# Regulators.net
KiCad netlist of a schematic drawn in Altium Designer
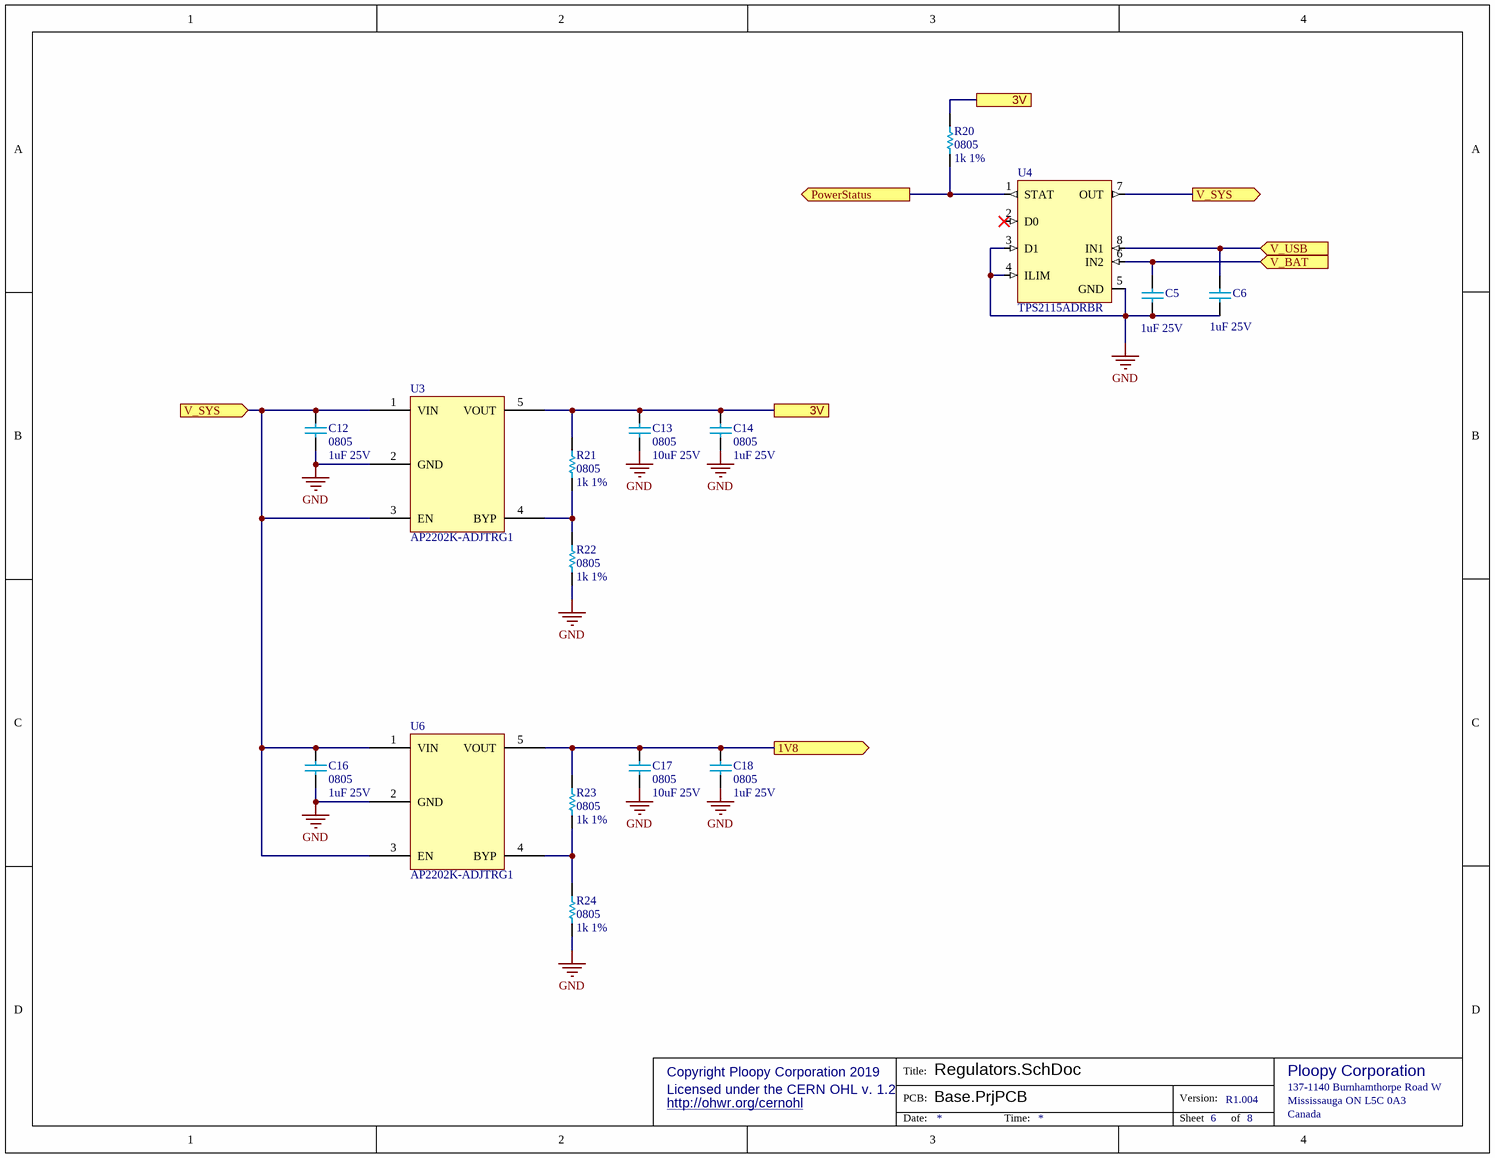
[diagram p0: Regulators.SchDoc]

(export (version "E")
  (design (tool "Eeschema 10.0.6"))
  (components
    (comp (ref "C5")
      (value "1uF 25V")
      (footprint "C0603")
      (description "0805, X5R or better")
      (fields (field (name "Comment") "0805"))
      (libsource (lib "Chip_Passives") (part "Cap 1uF 25V"))
    )
    (comp (ref "C6")
      (value "1uF 25V")
      (footprint "C0603")
      (description "0805, X5R or better")
      (fields (field (name "Comment") "0805"))
      (libsource (lib "Chip_Passives") (part "Cap 1uF 25V"))
    )
    (comp (ref "C12")
      (value "0805")
      (footprint "C0603")
      (description "0805, X5R or better")
      (fields (field (name "ALTIUM_VALUE") "1uF 25V"))
      (libsource (lib "Chip_Passives") (part "Cap 1uF 25V"))
    )
    (comp (ref "C13")
      (value "0805")
      (footprint "C0603")
      (description "0805, X5R or better")
      (fields (field (name "ALTIUM_VALUE") "10uF 25V"))
      (libsource (lib "Chip_Passives") (part "Cap 10uF 25V"))
    )
    (comp (ref "C14")
      (value "0805")
      (footprint "C0603")
      (description "0805, X5R or better")
      (fields (field (name "ALTIUM_VALUE") "1uF 25V"))
      (libsource (lib "Chip_Passives") (part "Cap 1uF 25V"))
    )
    (comp (ref "C16")
      (value "0805")
      (footprint "C0603")
      (description "0805, X5R or better")
      (fields (field (name "ALTIUM_VALUE") "1uF 25V"))
      (libsource (lib "Chip_Passives") (part "Cap 1uF 25V"))
    )
    (comp (ref "C17")
      (value "0805")
      (footprint "C0603")
      (description "0805, X5R or better")
      (fields (field (name "ALTIUM_VALUE") "10uF 25V"))
      (libsource (lib "Chip_Passives") (part "Cap 10uF 25V"))
    )
    (comp (ref "C18")
      (value "0805")
      (footprint "C0603")
      (description "0805, X5R or better")
      (fields (field (name "ALTIUM_VALUE") "1uF 25V"))
      (libsource (lib "Chip_Passives") (part "Cap 1uF 25V"))
    )
    (comp (ref "R20")
      (value "0805")
      (footprint "0603")
      (description "Chip resistor, 1/8W 100PPM")
      (fields (field (name "ALTIUM_VALUE") "1k 1%"))
      (libsource (lib "Chip_Passives") (part "Res 1k 1% 0805"))
    )
    (comp (ref "R21")
      (value "0805")
      (footprint "0603")
      (description "Chip resistor, 1/8W 100PPM")
      (fields (field (name "ALTIUM_VALUE") "1k 1%"))
      (libsource (lib "Chip_Passives") (part "Res 1k 1% 0805"))
    )
    (comp (ref "R22")
      (value "0805")
      (footprint "0603")
      (description "Chip resistor, 1/8W 100PPM")
      (fields (field (name "ALTIUM_VALUE") "1k 1%"))
      (libsource (lib "Chip_Passives") (part "Res 1k 1% 0805"))
    )
    (comp (ref "R23")
      (value "0805")
      (footprint "0603")
      (description "Chip resistor, 1/8W 100PPM")
      (fields (field (name "ALTIUM_VALUE") "1k 1%"))
      (libsource (lib "Chip_Passives") (part "Res 1k 1% 0805"))
    )
    (comp (ref "R24")
      (value "0805")
      (footprint "0603")
      (description "Chip resistor, 1/8W 100PPM")
      (fields (field (name "ALTIUM_VALUE") "1k 1%"))
      (libsource (lib "Chip_Passives") (part "Res 1k 1% 0805"))
    )
    (comp (ref "U3")
      (value "AP2202K-ADJTRG1")
      (footprint "AP2202 - SOT95P270X145-5N")
      (description "3.3V 150mA LDO regulator")
      (libsource (lib "PowerSupply") (part "AP2202K-3.3"))
    )
    (comp (ref "U4")
      (value "TPS2115ADRBR")
      (footprint "TSSOP-8")
      (libsource (lib "Schlib1") (part "TPS2115ADRBR"))
    )
    (comp (ref "U6")
      (value "AP2202K-ADJTRG1")
      (footprint "AP2202 - SOT95P270X145-5N")
      (description "3.3V 150mA LDO regulator")
      (libsource (lib "PowerSupply") (part "AP2202K-3.3"))
    )
  )
  (nets
    (net (code "1") (name "/1V8") (class "Default")
      (node (ref "C17") (pin "2") (pinfunction "2_2") (pintype "passive"))
      (node (ref "C18") (pin "2") (pinfunction "2_2") (pintype "passive"))
      (node (ref "R23") (pin "2") (pinfunction "2_2") (pintype "passive"))
      (node (ref "U6") (pin "5") (pinfunction "VOUT_5") (pintype "passive"))
    )
    (net (code "2") (name "/3V") (class "Default")
      (node (ref "C13") (pin "2") (pinfunction "2_2") (pintype "passive"))
      (node (ref "C14") (pin "2") (pinfunction "2_2") (pintype "passive"))
      (node (ref "R20") (pin "2") (pinfunction "2_2") (pintype "passive"))
      (node (ref "R21") (pin "2") (pinfunction "2_2") (pintype "passive"))
      (node (ref "U3") (pin "5") (pinfunction "VOUT_5") (pintype "passive"))
    )
    (net (code "3") (name "/PowerStatus") (class "Default")
      (node (ref "R20") (pin "1") (pinfunction "1_1") (pintype "passive"))
      (node (ref "U4") (pin "1") (pinfunction "STAT_1") (pintype "output"))
    )
    (net (code "4") (name "/V_BAT") (class "Default")
      (node (ref "C5") (pin "2") (pinfunction "2_2") (pintype "passive"))
      (node (ref "U4") (pin "6") (pinfunction "IN2_6") (pintype "input"))
    )
    (net (code "5") (name "/V_SYS") (class "Default")
      (node (ref "C12") (pin "2") (pinfunction "2_2") (pintype "passive"))
      (node (ref "C16") (pin "2") (pinfunction "2_2") (pintype "passive"))
      (node (ref "U3") (pin "1") (pinfunction "VIN_1") (pintype "passive"))
      (node (ref "U3") (pin "3") (pinfunction "EN_3") (pintype "passive"))
      (node (ref "U4") (pin "7") (pinfunction "OUT_7") (pintype "output"))
      (node (ref "U6") (pin "1") (pinfunction "VIN_1") (pintype "passive"))
      (node (ref "U6") (pin "3") (pinfunction "EN_3") (pintype "passive"))
    )
    (net (code "6") (name "/V_USB") (class "Default")
      (node (ref "C6") (pin "2") (pinfunction "2_2") (pintype "passive"))
      (node (ref "U4") (pin "8") (pinfunction "IN1_8") (pintype "input"))
    )
    (net (code "7") (name "GND") (class "Default")
      (node (ref "C12") (pin "1") (pinfunction "1_1") (pintype "passive"))
      (node (ref "C13") (pin "1") (pinfunction "1_1") (pintype "passive"))
      (node (ref "C14") (pin "1") (pinfunction "1_1") (pintype "passive"))
      (node (ref "C16") (pin "1") (pinfunction "1_1") (pintype "passive"))
      (node (ref "C17") (pin "1") (pinfunction "1_1") (pintype "passive"))
      (node (ref "C18") (pin "1") (pinfunction "1_1") (pintype "passive"))
      (node (ref "C5") (pin "1") (pinfunction "1_1") (pintype "passive"))
      (node (ref "C6") (pin "1") (pinfunction "1_1") (pintype "passive"))
      (node (ref "R22") (pin "1") (pinfunction "1_1") (pintype "passive"))
      (node (ref "R24") (pin "1") (pinfunction "1_1") (pintype "passive"))
      (node (ref "U3") (pin "2") (pinfunction "GND_2") (pintype "passive"))
      (node (ref "U4") (pin "3") (pinfunction "D1_3") (pintype "input"))
      (node (ref "U4") (pin "4") (pinfunction "ILIM_4") (pintype "input"))
      (node (ref "U4") (pin "5") (pinfunction "GND_5") (pintype "power_in"))
      (node (ref "U6") (pin "2") (pinfunction "GND_2") (pintype "passive"))
    )
    (net (code "8") (name "Net-(U3-BYP)") (class "Default")
      (node (ref "R21") (pin "1") (pinfunction "1_1") (pintype "passive"))
      (node (ref "R22") (pin "2") (pinfunction "2_2") (pintype "passive"))
      (node (ref "U3") (pin "4") (pinfunction "BYP_4") (pintype "passive"))
    )
    (net (code "9") (name "Net-(U6-BYP)") (class "Default")
      (node (ref "R23") (pin "1") (pinfunction "1_1") (pintype "passive"))
      (node (ref "R24") (pin "2") (pinfunction "2_2") (pintype "passive"))
      (node (ref "U6") (pin "4") (pinfunction "BYP_4") (pintype "passive"))
    )
    (net (code "10") (name "unconnected-(U4-D0-Pad2)") (class "Default")
      (node (ref "U4") (pin "2") (pinfunction "D0_2") (pintype "input+no_connect"))
    )
  )
)
